# 10_RS232_1.net
KiCad netlist of a schematic drawn in Altium Designer
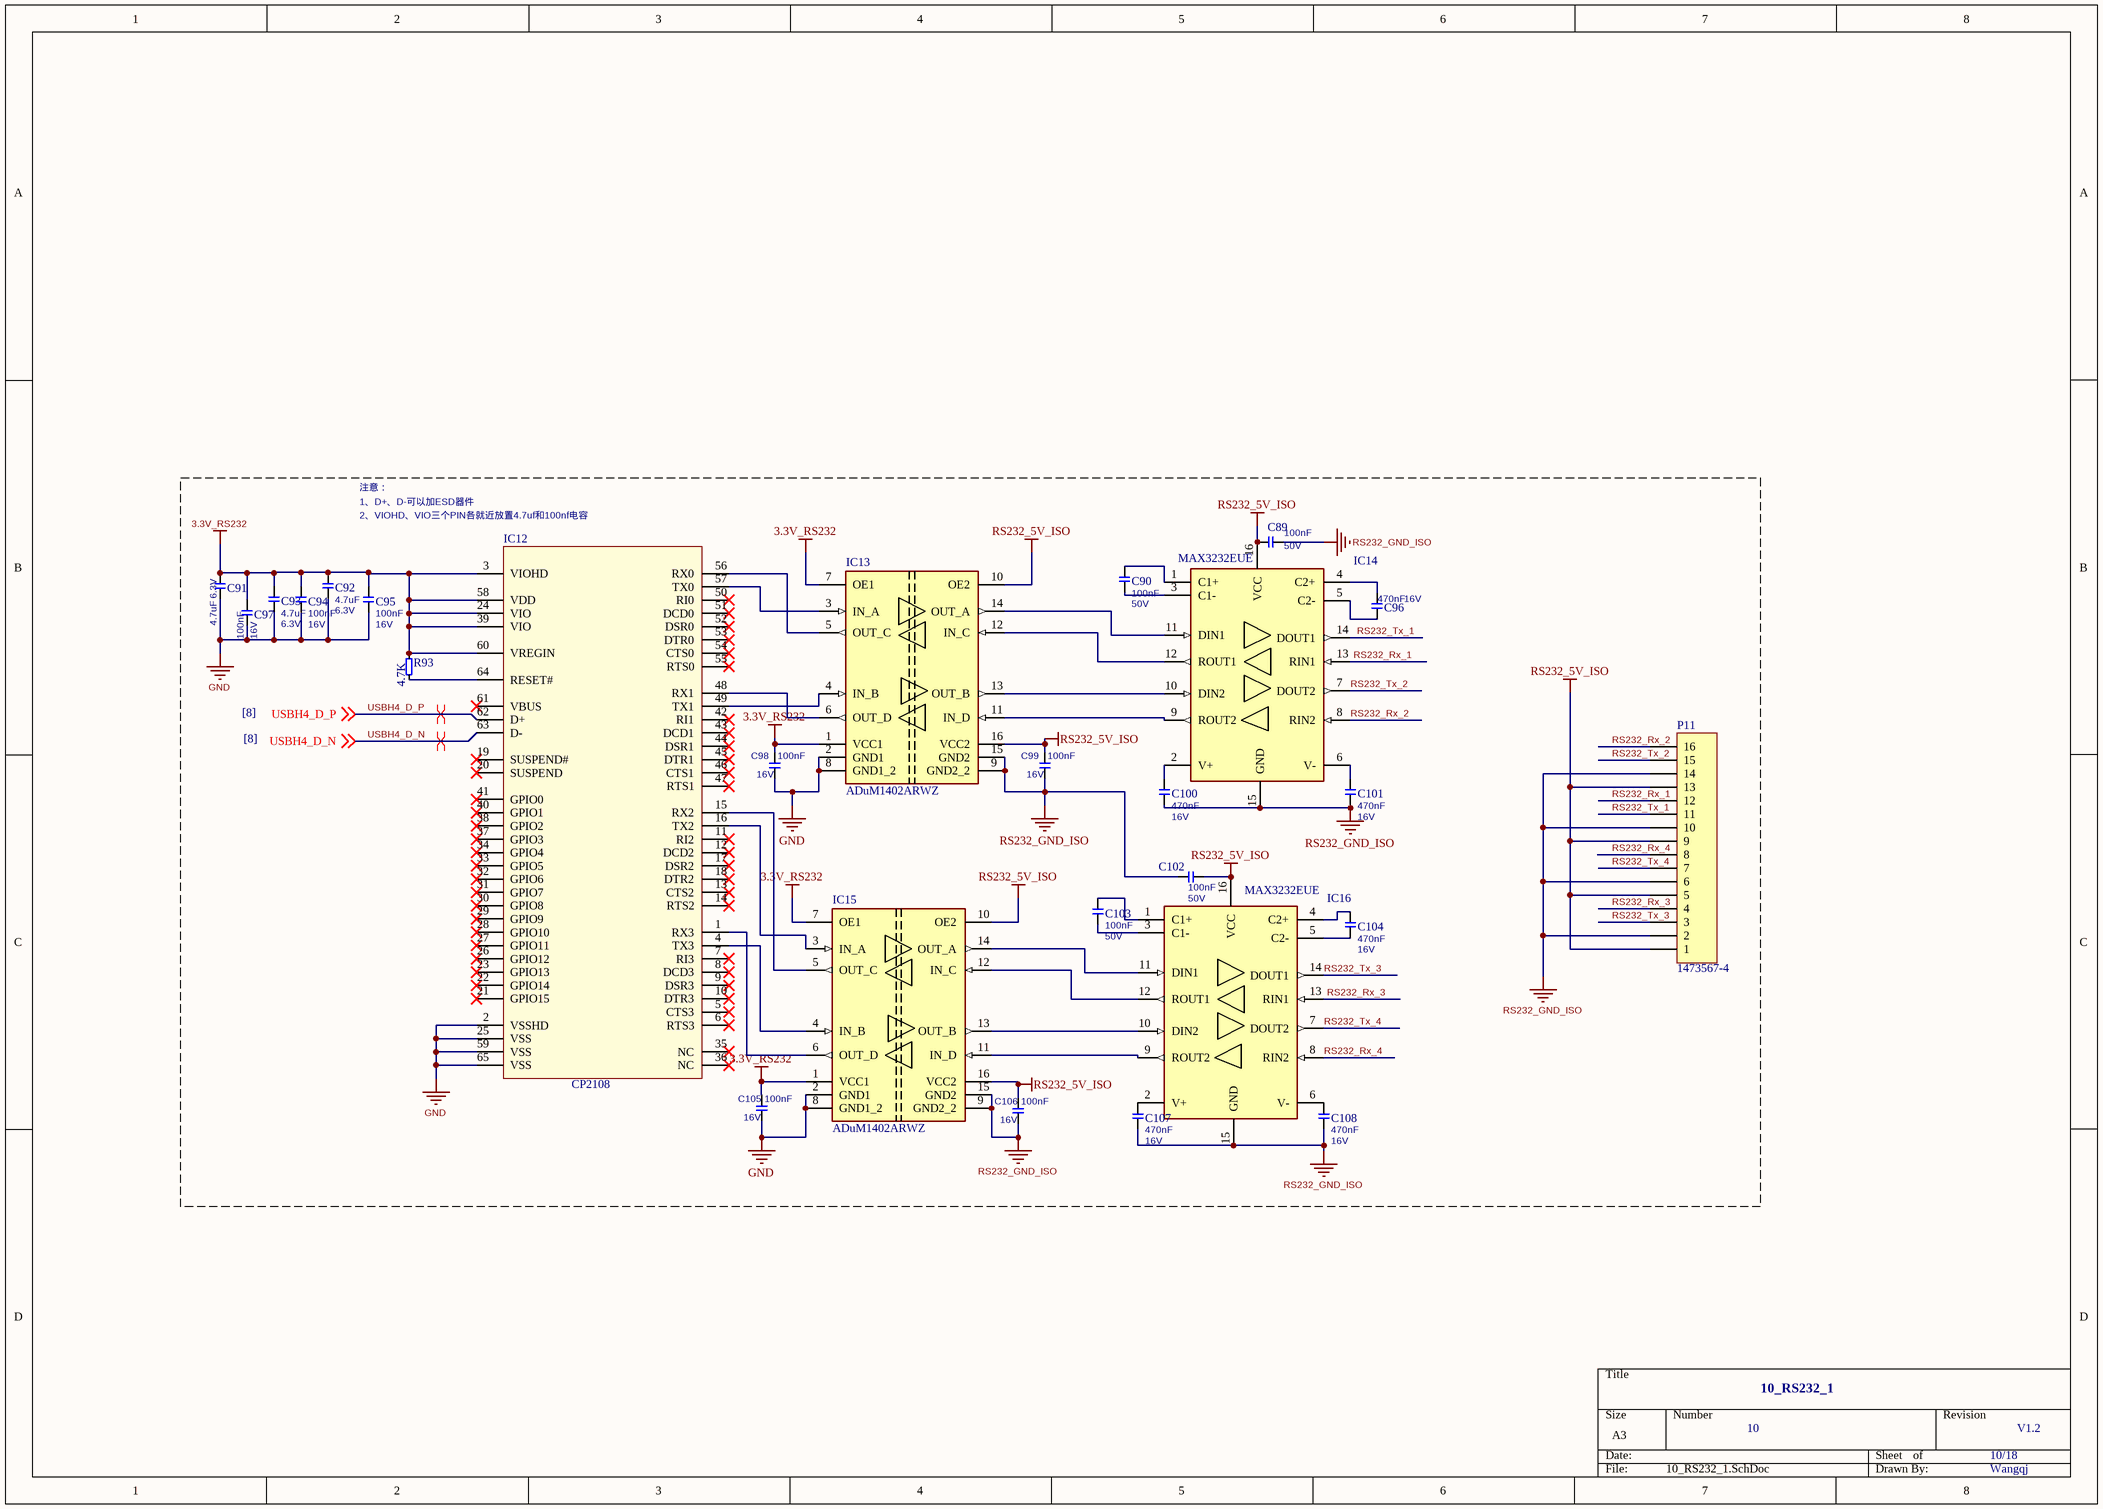
[diagram p0: 10_RS232_1.SchDoc]

(export (version "E")
  (design (tool "Eeschema 10.0.6"))
  (components
    (comp (ref "C89")
      (value "100nF")
      (footprint "T_CAPC0603X33N")
      (description "Capacitor Ceramic X7R 100nF 50V 20% 0603")
      (fields (field (name "TOLERANCE") "20%") (field (name "RATING") "50V"))
      (libsource (lib "Apalis Evaluation Board") (part "C-X7R-100nF-50V-20%-0603"))
    )
    (comp (ref "C90")
      (value "100nF")
      (footprint "T_CAPC0603X33N")
      (description "Capacitor Ceramic X7R 100nF 50V 20% 0603")
      (fields (field (name "TOLERANCE") "20%") (field (name "RATING") "50V"))
      (libsource (lib "Apalis Evaluation Board") (part "C-X7R-100nF-50V-20%-0603"))
    )
    (comp (ref "C91")
      (value "4.7uF")
      (footprint "T_CAPC0603X33N")
      (description "Capacitor Ceramic X5R 4.7uF 6.3V 20% 0603")
      (fields (field (name "TOLERANCE") "20%") (field (name "RATING") "6.3V"))
      (libsource (lib "Apalis Evaluation Board") (part "C-4.7uF-6.3V-20%-0603-X5R"))
    )
    (comp (ref "C92")
      (value "4.7uF")
      (footprint "T_CAPC0603X33N")
      (description "Capacitor Ceramic X5R 4.7uF 6.3V 20% 0603")
      (fields (field (name "TOLERANCE") "20%") (field (name "RATING") "6.3V"))
      (libsource (lib "Apalis Evaluation Board") (part "C-4.7uF-6.3V-20%-0603-X5R"))
    )
    (comp (ref "C93")
      (value "4.7uF")
      (footprint "T_CAPC0603X33N")
      (description "Capacitor Ceramic X5R 4.7uF 6.3V 20% 0603")
      (fields (field (name "TOLERANCE") "20%") (field (name "RATING") "6.3V"))
      (libsource (lib "Apalis Evaluation Board") (part "C-4.7uF-6.3V-20%-0603-X5R"))
    )
    (comp (ref "C94")
      (value "100nF")
      (footprint "T_CAPC0603X33N")
      (description "Capacitor Ceramic X7R 100nF 16V 10% 0603")
      (fields (field (name "TOLERANCE") "10%") (field (name "RATING") "16V"))
      (libsource (lib "Apalis Evaluation Board") (part "C-100nF-16V-10%-0603-X7R"))
    )
    (comp (ref "C95")
      (value "100nF")
      (footprint "T_CAPC0603X33N")
      (description "Capacitor Ceramic X7R 100nF 16V 10% 0603")
      (fields (field (name "TOLERANCE") "10%") (field (name "RATING") "16V"))
      (libsource (lib "Apalis Evaluation Board") (part "C-100nF-16V-10%-0603-X7R"))
    )
    (comp (ref "C96")
      (value "470nF")
      (footprint "T_CAPC0603X33N")
      (description "Capacitor Ceramic X7R 470nF 16V 10% 0603")
      (fields (field (name "TOLERANCE") "10%") (field (name "RATING") "16V"))
      (libsource (lib "Apalis Evaluation Board") (part "C-X7R-470nF-16V-10%-0603"))
    )
    (comp (ref "C97")
      (value "100nF")
      (footprint "T_CAPC0603X33N")
      (description "Capacitor Ceramic X7R 100nF 16V 10% 0603")
      (fields (field (name "TOLERANCE") "10%") (field (name "RATING") "16V"))
      (libsource (lib "Apalis Evaluation Board") (part "C-100nF-16V-10%-0603-X7R"))
    )
    (comp (ref "C98")
      (value "100nF")
      (footprint "T_CAPC0603X33N")
      (description "Capacitor Ceramic X7R 100nF 16V 10% 0603")
      (fields (field (name "TOLERANCE") "10%") (field (name "RATING") "16V"))
      (libsource (lib "Apalis Evaluation Board") (part "C-X7R-100nF-16V-10%-0603"))
    )
    (comp (ref "C99")
      (value "100nF")
      (footprint "T_CAPC0603X33N")
      (description "Capacitor Ceramic X7R 100nF 16V 10% 0603")
      (fields (field (name "TOLERANCE") "10%") (field (name "RATING") "16V"))
      (libsource (lib "Apalis Evaluation Board") (part "C-X7R-100nF-16V-10%-0603"))
    )
    (comp (ref "C100")
      (value "470nF")
      (footprint "T_CAPC0603X33N")
      (description "Capacitor Ceramic X7R 470nF 16V 10% 0603")
      (fields (field (name "TOLERANCE") "10%") (field (name "RATING") "16V"))
      (libsource (lib "Apalis Evaluation Board") (part "C-X7R-470nF-16V-10%-0603"))
    )
    (comp (ref "C101")
      (value "470nF")
      (footprint "T_CAPC0603X33N")
      (description "Capacitor Ceramic X7R 470nF 16V 10% 0603")
      (fields (field (name "TOLERANCE") "10%") (field (name "RATING") "16V"))
      (libsource (lib "Apalis Evaluation Board") (part "C-X7R-470nF-16V-10%-0603"))
    )
    (comp (ref "C102")
      (value "100nF")
      (footprint "T_CAPC0603X33N")
      (description "Capacitor Ceramic X7R 100nF 50V 20% 0603")
      (fields (field (name "TOLERANCE") "20%") (field (name "RATING") "50V"))
      (libsource (lib "Apalis Evaluation Board") (part "C-X7R-100nF-50V-20%-0603"))
    )
    (comp (ref "C103")
      (value "100nF")
      (footprint "T_CAPC0603X33N")
      (description "Capacitor Ceramic X7R 100nF 50V 20% 0603")
      (fields (field (name "TOLERANCE") "20%") (field (name "RATING") "50V"))
      (libsource (lib "Apalis Evaluation Board") (part "C-X7R-100nF-50V-20%-0603"))
    )
    (comp (ref "C104")
      (value "470nF")
      (footprint "T_CAPC0603X33N")
      (description "Capacitor Ceramic X7R 470nF 16V 10% 0603")
      (fields (field (name "TOLERANCE") "10%") (field (name "RATING") "16V"))
      (libsource (lib "Apalis Evaluation Board") (part "C-X7R-470nF-16V-10%-0603"))
    )
    (comp (ref "C105")
      (value "100nF")
      (footprint "T_CAPC0603X33N")
      (description "Capacitor Ceramic X7R 100nF 16V 10% 0603")
      (fields (field (name "TOLERANCE") "10%") (field (name "RATING") "16V"))
      (libsource (lib "Apalis Evaluation Board") (part "C-X7R-100nF-16V-10%-0603"))
    )
    (comp (ref "C106")
      (value "100nF")
      (footprint "T_CAPC0603X33N")
      (description "Capacitor Ceramic X7R 100nF 16V 10% 0603")
      (fields (field (name "TOLERANCE") "10%") (field (name "RATING") "16V"))
      (libsource (lib "Apalis Evaluation Board") (part "C-X7R-100nF-16V-10%-0603"))
    )
    (comp (ref "C107")
      (value "470nF")
      (footprint "T_CAPC0603X33N")
      (description "Capacitor Ceramic X7R 470nF 16V 10% 0603")
      (fields (field (name "TOLERANCE") "10%") (field (name "RATING") "16V"))
      (libsource (lib "Apalis Evaluation Board") (part "C-X7R-470nF-16V-10%-0603"))
    )
    (comp (ref "C108")
      (value "470nF")
      (footprint "T_CAPC0603X33N")
      (description "Capacitor Ceramic X7R 470nF 16V 10% 0603")
      (fields (field (name "TOLERANCE") "10%") (field (name "RATING") "16V"))
      (libsource (lib "Apalis Evaluation Board") (part "C-X7R-470nF-16V-10%-0603"))
    )
    (comp (ref "IC12")
      (value "CP2108")
      (footprint "QFN50P900X900X90_HS-65N")
      (description "Single-Chip USB To Quad UART Bridge")
      (fields (field (name "MANUCFACTURER PART NO.") "CP2108"))
      (libsource (lib "Apalis Evaluation Board") (part "IC-SILICON-CP2108"))
    )
    (comp (ref "IC13")
      (value "ADuM1402ARWZ")
      (footprint "T_AD_ADuM1300ARW")
      (description "Digital Isolator")
      (libsource (lib "Apalis Evaluation Board") (part "IC-AD-ADuM1402ARWZ"))
    )
    (comp (ref "IC14")
      (value "MAX3232EUE")
      (footprint "LC-TSSOP-16")
      (description "RS232")
      (libsource (lib "Apalis Evaluation Board") (part "IC-MAXIM-MAX3232"))
    )
    (comp (ref "IC15")
      (value "ADuM1402ARWZ")
      (footprint "T_AD_ADuM1300ARW")
      (description "Digital Isolator")
      (libsource (lib "Apalis Evaluation Board") (part "IC-AD-ADuM1402ARWZ"))
    )
    (comp (ref "IC16")
      (value "MAX3232EUE")
      (footprint "LC-TSSOP-16")
      (description "RS232")
      (libsource (lib "Apalis Evaluation Board") (part "IC-MAXIM-MAX3232"))
    )
    (comp (ref "P11")
      (value "1473567-4")
      (footprint "147-4")
      (description "泰科4P端子")
      (fields (field (name "PUBLISHER") "Altium Limited"))
      (libsource (lib "Miscellaneous Connectors") (part "MHDR1X16"))
    )
    (comp (ref "R93")
      (value "4.7K")
      (footprint "t_RESC0603X30N")
      (description "Resistor 4.7 Kohm 63mW 5% 0603")
      (fields (field (name "TOLERANCE") "5%"))
      (libsource (lib "Apalis Evaluation Board") (part "R-4.7kR-63mW-5%-0603"))
    )
  )
  (nets
    (net (code "1") (name "/RS232_Rx_1") (class "Default")
      (node (ref "IC14") (pin "13") (pinfunction "RIN1_13") (pintype "input"))
      (node (ref "P11") (pin "12") (pinfunction "12_12") (pintype "passive"))
    )
    (net (code "2") (name "/RS232_Rx_2") (class "Default")
      (node (ref "IC14") (pin "8") (pinfunction "RIN2_8") (pintype "input"))
      (node (ref "P11") (pin "16") (pinfunction "16_16") (pintype "passive"))
    )
    (net (code "3") (name "/RS232_Rx_3") (class "Default")
      (node (ref "IC16") (pin "13") (pinfunction "RIN1_13") (pintype "input"))
      (node (ref "P11") (pin "4") (pinfunction "4_4") (pintype "passive"))
    )
    (net (code "4") (name "/RS232_Rx_4") (class "Default")
      (node (ref "IC16") (pin "8") (pinfunction "RIN2_8") (pintype "input"))
      (node (ref "P11") (pin "8") (pinfunction "8_8") (pintype "passive"))
    )
    (net (code "5") (name "/RS232_Tx_1") (class "Default")
      (node (ref "IC14") (pin "14") (pinfunction "DOUT1_14") (pintype "output"))
      (node (ref "P11") (pin "11") (pinfunction "11_11") (pintype "passive"))
    )
    (net (code "6") (name "/RS232_Tx_2") (class "Default")
      (node (ref "IC14") (pin "7") (pinfunction "DOUT2_7") (pintype "output"))
      (node (ref "P11") (pin "15") (pinfunction "15_15") (pintype "passive"))
    )
    (net (code "7") (name "/RS232_Tx_3") (class "Default")
      (node (ref "IC16") (pin "14") (pinfunction "DOUT1_14") (pintype "output"))
      (node (ref "P11") (pin "3") (pinfunction "3_3") (pintype "passive"))
    )
    (net (code "8") (name "/RS232_Tx_4") (class "Default")
      (node (ref "IC16") (pin "7") (pinfunction "DOUT2_7") (pintype "output"))
      (node (ref "P11") (pin "7") (pinfunction "7_7") (pintype "passive"))
    )
    (net (code "9") (name "3.3V_RS232") (class "Default")
      (node (ref "C105") (pin "2") (pinfunction "2_2") (pintype "passive"))
      (node (ref "C91") (pin "2") (pinfunction "2_2") (pintype "passive"))
      (node (ref "C92") (pin "2") (pinfunction "2_2") (pintype "passive"))
      (node (ref "C93") (pin "2") (pinfunction "2_2") (pintype "passive"))
      (node (ref "C94") (pin "2") (pinfunction "2_2") (pintype "passive"))
      (node (ref "C95") (pin "2") (pinfunction "2_2") (pintype "passive"))
      (node (ref "C97") (pin "2") (pinfunction "2_2") (pintype "passive"))
      (node (ref "C98") (pin "2") (pinfunction "2_2") (pintype "passive"))
      (node (ref "IC12") (pin "24") (pinfunction "VIO_24") (pintype "power_in"))
      (node (ref "IC12") (pin "3") (pinfunction "VIOHD_3") (pintype "power_in"))
      (node (ref "IC12") (pin "39") (pinfunction "VIO_39") (pintype "passive"))
      (node (ref "IC12") (pin "58") (pinfunction "VDD_58") (pintype "passive"))
      (node (ref "IC12") (pin "60") (pinfunction "VREGIN_60") (pintype "passive"))
      (node (ref "IC13") (pin "1") (pinfunction "VCC1_1") (pintype "passive"))
      (node (ref "IC13") (pin "7") (pinfunction "OE1_7") (pintype "passive"))
      (node (ref "IC15") (pin "1") (pinfunction "VCC1_1") (pintype "passive"))
      (node (ref "IC15") (pin "7") (pinfunction "OE1_7") (pintype "passive"))
      (node (ref "R93") (pin "2") (pinfunction "2_2") (pintype "passive"))
    )
    (net (code "10") (name "GND") (class "Default")
      (node (ref "C105") (pin "1") (pinfunction "1_1") (pintype "passive"))
      (node (ref "C91") (pin "1") (pinfunction "1_1") (pintype "passive"))
      (node (ref "C92") (pin "1") (pinfunction "1_1") (pintype "passive"))
      (node (ref "C93") (pin "1") (pinfunction "1_1") (pintype "passive"))
      (node (ref "C94") (pin "1") (pinfunction "1_1") (pintype "passive"))
      (node (ref "C95") (pin "1") (pinfunction "1_1") (pintype "passive"))
      (node (ref "C97") (pin "1") (pinfunction "1_1") (pintype "passive"))
      (node (ref "C98") (pin "1") (pinfunction "1_1") (pintype "passive"))
      (node (ref "IC12") (pin "2") (pinfunction "VSSHD_2") (pintype "passive"))
      (node (ref "IC12") (pin "25") (pinfunction "VSS_25") (pintype "power_in"))
      (node (ref "IC12") (pin "59") (pinfunction "VSS_59") (pintype "passive"))
      (node (ref "IC12") (pin "65") (pinfunction "VSS_65") (pintype "passive"))
      (node (ref "IC13") (pin "2") (pinfunction "GND1_2") (pintype "power_in"))
      (node (ref "IC13") (pin "8") (pinfunction "GND1_2_8") (pintype "power_in"))
      (node (ref "IC15") (pin "2") (pinfunction "GND1_2") (pintype "power_in"))
      (node (ref "IC15") (pin "8") (pinfunction "GND1_2_8") (pintype "power_in"))
    )
    (net (code "11") (name "Net-(IC12-RESET#)") (class "Default")
      (node (ref "IC12") (pin "64") (pinfunction "RESET#_64") (pintype "passive"))
      (node (ref "R93") (pin "1") (pinfunction "1_1") (pintype "passive"))
    )
    (net (code "12") (name "Net-(IC12-RX0)") (class "Default")
      (node (ref "IC12") (pin "56") (pinfunction "RX0_56") (pintype "passive"))
      (node (ref "IC13") (pin "5") (pinfunction "OUT_C_5") (pintype "output"))
    )
    (net (code "13") (name "Net-(IC12-RX1)") (class "Default")
      (node (ref "IC12") (pin "48") (pinfunction "RX1_48") (pintype "passive"))
      (node (ref "IC13") (pin "6") (pinfunction "OUT_D_6") (pintype "output"))
    )
    (net (code "14") (name "Net-(IC12-RX2)") (class "Default")
      (node (ref "IC12") (pin "15") (pinfunction "RX2_15") (pintype "passive"))
      (node (ref "IC15") (pin "5") (pinfunction "OUT_C_5") (pintype "output"))
    )
    (net (code "15") (name "Net-(IC12-RX3)") (class "Default")
      (node (ref "IC12") (pin "1") (pinfunction "RX3_1") (pintype "passive"))
      (node (ref "IC15") (pin "6") (pinfunction "OUT_D_6") (pintype "output"))
    )
    (net (code "16") (name "Net-(IC12-TX0)") (class "Default")
      (node (ref "IC12") (pin "57") (pinfunction "TX0_57") (pintype "passive"))
      (node (ref "IC13") (pin "3") (pinfunction "IN_A_3") (pintype "input"))
    )
    (net (code "17") (name "Net-(IC12-TX1)") (class "Default")
      (node (ref "IC12") (pin "49") (pinfunction "TX1_49") (pintype "passive"))
      (node (ref "IC13") (pin "4") (pinfunction "IN_B_4") (pintype "input"))
    )
    (net (code "18") (name "Net-(IC12-TX2)") (class "Default")
      (node (ref "IC12") (pin "16") (pinfunction "TX2_16") (pintype "passive"))
      (node (ref "IC15") (pin "3") (pinfunction "IN_A_3") (pintype "input"))
    )
    (net (code "19") (name "Net-(IC12-TX3)") (class "Default")
      (node (ref "IC12") (pin "4") (pinfunction "TX3_4") (pintype "passive"))
      (node (ref "IC15") (pin "4") (pinfunction "IN_B_4") (pintype "input"))
    )
    (net (code "20") (name "Net-(IC13-IN_C)") (class "Default")
      (node (ref "IC13") (pin "12") (pinfunction "IN_C_12") (pintype "input"))
      (node (ref "IC14") (pin "12") (pinfunction "ROUT1_12") (pintype "output"))
    )
    (net (code "21") (name "Net-(IC13-IN_D)") (class "Default")
      (node (ref "IC13") (pin "11") (pinfunction "IN_D_11") (pintype "input"))
      (node (ref "IC14") (pin "9") (pinfunction "ROUT2_9") (pintype "output"))
    )
    (net (code "22") (name "Net-(IC13-OUT_A)") (class "Default")
      (node (ref "IC13") (pin "14") (pinfunction "OUT_A_14") (pintype "output"))
      (node (ref "IC14") (pin "11") (pinfunction "DIN1_11") (pintype "input"))
    )
    (net (code "23") (name "Net-(IC13-OUT_B)") (class "Default")
      (node (ref "IC13") (pin "13") (pinfunction "OUT_B_13") (pintype "output"))
      (node (ref "IC14") (pin "10") (pinfunction "DIN2_10") (pintype "input"))
    )
    (net (code "24") (name "Net-(IC14-C1+)") (class "Default")
      (node (ref "C90") (pin "2") (pinfunction "2_2") (pintype "passive"))
      (node (ref "IC14") (pin "1") (pinfunction "C1+_1") (pintype "passive"))
    )
    (net (code "25") (name "Net-(IC14-C1-)") (class "Default")
      (node (ref "C90") (pin "1") (pinfunction "1_1") (pintype "passive"))
      (node (ref "IC14") (pin "3") (pinfunction "C1-_3") (pintype "power_in"))
    )
    (net (code "26") (name "Net-(IC14-C2+)") (class "Default")
      (node (ref "C96") (pin "2") (pinfunction "2_2") (pintype "passive"))
      (node (ref "IC14") (pin "4") (pinfunction "C2+_4") (pintype "passive"))
    )
    (net (code "27") (name "Net-(IC14-C2-)") (class "Default")
      (node (ref "C96") (pin "1") (pinfunction "1_1") (pintype "passive"))
      (node (ref "IC14") (pin "5") (pinfunction "C2-_5") (pintype "power_in"))
    )
    (net (code "28") (name "Net-(IC14-V+)") (class "Default")
      (node (ref "C100") (pin "2") (pinfunction "2_2") (pintype "passive"))
      (node (ref "IC14") (pin "2") (pinfunction "V+_2") (pintype "passive"))
    )
    (net (code "29") (name "Net-(IC14-V-)") (class "Default")
      (node (ref "C101") (pin "2") (pinfunction "2_2") (pintype "passive"))
      (node (ref "IC14") (pin "6") (pinfunction "V-_6") (pintype "passive"))
    )
    (net (code "30") (name "Net-(IC15-IN_C)") (class "Default")
      (node (ref "IC15") (pin "12") (pinfunction "IN_C_12") (pintype "input"))
      (node (ref "IC16") (pin "12") (pinfunction "ROUT1_12") (pintype "output"))
    )
    (net (code "31") (name "Net-(IC15-IN_D)") (class "Default")
      (node (ref "IC15") (pin "11") (pinfunction "IN_D_11") (pintype "input"))
      (node (ref "IC16") (pin "9") (pinfunction "ROUT2_9") (pintype "output"))
    )
    (net (code "32") (name "Net-(IC15-OUT_A)") (class "Default")
      (node (ref "IC15") (pin "14") (pinfunction "OUT_A_14") (pintype "output"))
      (node (ref "IC16") (pin "11") (pinfunction "DIN1_11") (pintype "input"))
    )
    (net (code "33") (name "Net-(IC15-OUT_B)") (class "Default")
      (node (ref "IC15") (pin "13") (pinfunction "OUT_B_13") (pintype "output"))
      (node (ref "IC16") (pin "10") (pinfunction "DIN2_10") (pintype "input"))
    )
    (net (code "34") (name "Net-(IC16-C1+)") (class "Default")
      (node (ref "C103") (pin "2") (pinfunction "2_2") (pintype "passive"))
      (node (ref "IC16") (pin "1") (pinfunction "C1+_1") (pintype "passive"))
    )
    (net (code "35") (name "Net-(IC16-C1-)") (class "Default")
      (node (ref "C103") (pin "1") (pinfunction "1_1") (pintype "passive"))
      (node (ref "IC16") (pin "3") (pinfunction "C1-_3") (pintype "power_in"))
    )
    (net (code "36") (name "Net-(IC16-C2+)") (class "Default")
      (node (ref "C104") (pin "2") (pinfunction "2_2") (pintype "passive"))
      (node (ref "IC16") (pin "4") (pinfunction "C2+_4") (pintype "passive"))
    )
    (net (code "37") (name "Net-(IC16-C2-)") (class "Default")
      (node (ref "C104") (pin "1") (pinfunction "1_1") (pintype "passive"))
      (node (ref "IC16") (pin "5") (pinfunction "C2-_5") (pintype "power_in"))
    )
    (net (code "38") (name "Net-(IC16-V+)") (class "Default")
      (node (ref "C107") (pin "2") (pinfunction "2_2") (pintype "passive"))
      (node (ref "IC16") (pin "2") (pinfunction "V+_2") (pintype "passive"))
    )
    (net (code "39") (name "Net-(IC16-V-)") (class "Default")
      (node (ref "C108") (pin "2") (pinfunction "2_2") (pintype "passive"))
      (node (ref "IC16") (pin "6") (pinfunction "V-_6") (pintype "passive"))
    )
    (net (code "40") (name "RS232_5V_ISO") (class "Default")
      (node (ref "C102") (pin "1") (pinfunction "1_1") (pintype "passive"))
      (node (ref "C106") (pin "2") (pinfunction "2_2") (pintype "passive"))
      (node (ref "C89") (pin "2") (pinfunction "2_2") (pintype "passive"))
      (node (ref "C99") (pin "2") (pinfunction "2_2") (pintype "passive"))
      (node (ref "IC13") (pin "10") (pinfunction "OE2_10") (pintype "passive"))
      (node (ref "IC13") (pin "16") (pinfunction "VCC2_16") (pintype "passive"))
      (node (ref "IC14") (pin "16") (pinfunction "VCC_16") (pintype "power_in"))
      (node (ref "IC15") (pin "10") (pinfunction "OE2_10") (pintype "passive"))
      (node (ref "IC15") (pin "16") (pinfunction "VCC2_16") (pintype "passive"))
      (node (ref "IC16") (pin "16") (pinfunction "VCC_16") (pintype "power_in"))
      (node (ref "P11") (pin "1") (pinfunction "1_1") (pintype "passive"))
      (node (ref "P11") (pin "13") (pinfunction "13_13") (pintype "passive"))
      (node (ref "P11") (pin "5") (pinfunction "5_5") (pintype "passive"))
      (node (ref "P11") (pin "9") (pinfunction "9_9") (pintype "passive"))
    )
    (net (code "41") (name "RS232_GND_ISO") (class "Default")
      (node (ref "C100") (pin "1") (pinfunction "1_1") (pintype "passive"))
      (node (ref "C101") (pin "1") (pinfunction "1_1") (pintype "passive"))
      (node (ref "C102") (pin "2") (pinfunction "2_2") (pintype "passive"))
      (node (ref "C106") (pin "1") (pinfunction "1_1") (pintype "passive"))
      (node (ref "C107") (pin "1") (pinfunction "1_1") (pintype "passive"))
      (node (ref "C108") (pin "1") (pinfunction "1_1") (pintype "passive"))
      (node (ref "C89") (pin "1") (pinfunction "1_1") (pintype "passive"))
      (node (ref "C99") (pin "1") (pinfunction "1_1") (pintype "passive"))
      (node (ref "IC13") (pin "15") (pinfunction "GND2_15") (pintype "power_in"))
      (node (ref "IC13") (pin "9") (pinfunction "GND2_2_9") (pintype "power_in"))
      (node (ref "IC14") (pin "15") (pinfunction "GND_15") (pintype "power_in"))
      (node (ref "IC15") (pin "15") (pinfunction "GND2_15") (pintype "power_in"))
      (node (ref "IC15") (pin "9") (pinfunction "GND2_2_9") (pintype "power_in"))
      (node (ref "IC16") (pin "15") (pinfunction "GND_15") (pintype "power_in"))
      (node (ref "P11") (pin "10") (pinfunction "10_10") (pintype "passive"))
      (node (ref "P11") (pin "14") (pinfunction "14_14") (pintype "passive"))
      (node (ref "P11") (pin "2") (pinfunction "2_2") (pintype "passive"))
      (node (ref "P11") (pin "6") (pinfunction "6_6") (pintype "passive"))
    )
    (net (code "42") (name "USBH4_D_N") (class "Default")
      (node (ref "IC12") (pin "63") (pinfunction "D-_63") (pintype "passive"))
    )
    (net (code "43") (name "USBH4_D_P") (class "Default")
      (node (ref "IC12") (pin "62") (pinfunction "D+_62") (pintype "passive"))
    )
    (net (code "44") (name "unconnected-(IC12-CTS0-Pad54)") (class "Default")
      (node (ref "IC12") (pin "54") (pinfunction "CTS0_54") (pintype "passive+no_connect"))
    )
    (net (code "45") (name "unconnected-(IC12-CTS1-Pad46)") (class "Default")
      (node (ref "IC12") (pin "46") (pinfunction "CTS1_46") (pintype "passive+no_connect"))
    )
    (net (code "46") (name "unconnected-(IC12-CTS2-Pad13)") (class "Default")
      (node (ref "IC12") (pin "13") (pinfunction "CTS2_13") (pintype "passive+no_connect"))
    )
    (net (code "47") (name "unconnected-(IC12-CTS3-Pad5)") (class "Default")
      (node (ref "IC12") (pin "5") (pinfunction "CTS3_5") (pintype "passive+no_connect"))
    )
    (net (code "48") (name "unconnected-(IC12-DCD0-Pad51)") (class "Default")
      (node (ref "IC12") (pin "51") (pinfunction "DCD0_51") (pintype "passive+no_connect"))
    )
    (net (code "49") (name "unconnected-(IC12-DCD1-Pad43)") (class "Default")
      (node (ref "IC12") (pin "43") (pinfunction "DCD1_43") (pintype "passive+no_connect"))
    )
    (net (code "50") (name "unconnected-(IC12-DCD2-Pad12)") (class "Default")
      (node (ref "IC12") (pin "12") (pinfunction "DCD2_12") (pintype "passive+no_connect"))
    )
    (net (code "51") (name "unconnected-(IC12-DCD3-Pad8)") (class "Default")
      (node (ref "IC12") (pin "8") (pinfunction "DCD3_8") (pintype "passive+no_connect"))
    )
    (net (code "52") (name "unconnected-(IC12-DSR0-Pad52)") (class "Default")
      (node (ref "IC12") (pin "52") (pinfunction "DSR0_52") (pintype "passive+no_connect"))
    )
    (net (code "53") (name "unconnected-(IC12-DSR1-Pad44)") (class "Default")
      (node (ref "IC12") (pin "44") (pinfunction "DSR1_44") (pintype "passive+no_connect"))
    )
    (net (code "54") (name "unconnected-(IC12-DSR2-Pad17)") (class "Default")
      (node (ref "IC12") (pin "17") (pinfunction "DSR2_17") (pintype "passive+no_connect"))
    )
    (net (code "55") (name "unconnected-(IC12-DSR3-Pad9)") (class "Default")
      (node (ref "IC12") (pin "9") (pinfunction "DSR3_9") (pintype "passive+no_connect"))
    )
    (net (code "56") (name "unconnected-(IC12-DTR0-Pad53)") (class "Default")
      (node (ref "IC12") (pin "53") (pinfunction "DTR0_53") (pintype "passive+no_connect"))
    )
    (net (code "57") (name "unconnected-(IC12-DTR1-Pad45)") (class "Default")
      (node (ref "IC12") (pin "45") (pinfunction "DTR1_45") (pintype "passive+no_connect"))
    )
    (net (code "58") (name "unconnected-(IC12-DTR2-Pad18)") (class "Default")
      (node (ref "IC12") (pin "18") (pinfunction "DTR2_18") (pintype "passive+no_connect"))
    )
    (net (code "59") (name "unconnected-(IC12-DTR3-Pad10)") (class "Default")
      (node (ref "IC12") (pin "10") (pinfunction "DTR3_10") (pintype "passive+no_connect"))
    )
    (net (code "60") (name "unconnected-(IC12-GPIO0-Pad41)") (class "Default")
      (node (ref "IC12") (pin "41") (pinfunction "GPIO0_41") (pintype "passive+no_connect"))
    )
    (net (code "61") (name "unconnected-(IC12-GPIO1-Pad40)") (class "Default")
      (node (ref "IC12") (pin "40") (pinfunction "GPIO1_40") (pintype "passive+no_connect"))
    )
    (net (code "62") (name "unconnected-(IC12-GPIO2-Pad38)") (class "Default")
      (node (ref "IC12") (pin "38") (pinfunction "GPIO2_38") (pintype "passive+no_connect"))
    )
    (net (code "63") (name "unconnected-(IC12-GPIO3-Pad37)") (class "Default")
      (node (ref "IC12") (pin "37") (pinfunction "GPIO3_37") (pintype "passive+no_connect"))
    )
    (net (code "64") (name "unconnected-(IC12-GPIO4-Pad34)") (class "Default")
      (node (ref "IC12") (pin "34") (pinfunction "GPIO4_34") (pintype "passive+no_connect"))
    )
    (net (code "65") (name "unconnected-(IC12-GPIO5-Pad33)") (class "Default")
      (node (ref "IC12") (pin "33") (pinfunction "GPIO5_33") (pintype "passive+no_connect"))
    )
    (net (code "66") (name "unconnected-(IC12-GPIO6-Pad32)") (class "Default")
      (node (ref "IC12") (pin "32") (pinfunction "GPIO6_32") (pintype "passive+no_connect"))
    )
    (net (code "67") (name "unconnected-(IC12-GPIO7-Pad31)") (class "Default")
      (node (ref "IC12") (pin "31") (pinfunction "GPIO7_31") (pintype "passive+no_connect"))
    )
    (net (code "68") (name "unconnected-(IC12-GPIO8-Pad30)") (class "Default")
      (node (ref "IC12") (pin "30") (pinfunction "GPIO8_30") (pintype "passive+no_connect"))
    )
    (net (code "69") (name "unconnected-(IC12-GPIO9-Pad29)") (class "Default")
      (node (ref "IC12") (pin "29") (pinfunction "GPIO9_29") (pintype "passive+no_connect"))
    )
    (net (code "70") (name "unconnected-(IC12-GPIO10-Pad28)") (class "Default")
      (node (ref "IC12") (pin "28") (pinfunction "GPIO10_28") (pintype "passive+no_connect"))
    )
    (net (code "71") (name "unconnected-(IC12-GPIO11-Pad27)") (class "Default")
      (node (ref "IC12") (pin "27") (pinfunction "GPIO11_27") (pintype "passive+no_connect"))
    )
    (net (code "72") (name "unconnected-(IC12-GPIO12-Pad26)") (class "Default")
      (node (ref "IC12") (pin "26") (pinfunction "GPIO12_26") (pintype "passive+no_connect"))
    )
    (net (code "73") (name "unconnected-(IC12-GPIO13-Pad23)") (class "Default")
      (node (ref "IC12") (pin "23") (pinfunction "GPIO13_23") (pintype "passive+no_connect"))
    )
    (net (code "74") (name "unconnected-(IC12-GPIO14-Pad22)") (class "Default")
      (node (ref "IC12") (pin "22") (pinfunction "GPIO14_22") (pintype "passive+no_connect"))
    )
    (net (code "75") (name "unconnected-(IC12-GPIO15-Pad21)") (class "Default")
      (node (ref "IC12") (pin "21") (pinfunction "GPIO15_21") (pintype "passive+no_connect"))
    )
    (net (code "76") (name "unconnected-(IC12-NC-Pad35)") (class "Default")
      (node (ref "IC12") (pin "35") (pinfunction "NC_35") (pintype "passive+no_connect"))
    )
    (net (code "77") (name "unconnected-(IC12-NC-Pad36)") (class "Default")
      (node (ref "IC12") (pin "36") (pinfunction "NC_36") (pintype "passive+no_connect"))
    )
    (net (code "78") (name "unconnected-(IC12-RI0-Pad50)") (class "Default")
      (node (ref "IC12") (pin "50") (pinfunction "RI0_50") (pintype "passive+no_connect"))
    )
    (net (code "79") (name "unconnected-(IC12-RI1-Pad42)") (class "Default")
      (node (ref "IC12") (pin "42") (pinfunction "RI1_42") (pintype "passive+no_connect"))
    )
    (net (code "80") (name "unconnected-(IC12-RI2-Pad11)") (class "Default")
      (node (ref "IC12") (pin "11") (pinfunction "RI2_11") (pintype "passive+no_connect"))
    )
    (net (code "81") (name "unconnected-(IC12-RI3-Pad7)") (class "Default")
      (node (ref "IC12") (pin "7") (pinfunction "RI3_7") (pintype "passive+no_connect"))
    )
    (net (code "82") (name "unconnected-(IC12-RTS0-Pad55)") (class "Default")
      (node (ref "IC12") (pin "55") (pinfunction "RTS0_55") (pintype "passive+no_connect"))
    )
    (net (code "83") (name "unconnected-(IC12-RTS1-Pad47)") (class "Default")
      (node (ref "IC12") (pin "47") (pinfunction "RTS1_47") (pintype "passive+no_connect"))
    )
    (net (code "84") (name "unconnected-(IC12-RTS2-Pad14)") (class "Default")
      (node (ref "IC12") (pin "14") (pinfunction "RTS2_14") (pintype "passive+no_connect"))
    )
    (net (code "85") (name "unconnected-(IC12-RTS3-Pad6)") (class "Default")
      (node (ref "IC12") (pin "6") (pinfunction "RTS3_6") (pintype "passive+no_connect"))
    )
    (net (code "86") (name "unconnected-(IC12-SUSPEND#-Pad19)") (class "Default")
      (node (ref "IC12") (pin "19") (pinfunction "SUSPEND#_19") (pintype "passive+no_connect"))
    )
    (net (code "87") (name "unconnected-(IC12-SUSPEND-Pad20)") (class "Default")
      (node (ref "IC12") (pin "20") (pinfunction "SUSPEND_20") (pintype "passive+no_connect"))
    )
    (net (code "88") (name "unconnected-(IC12-VBUS-Pad61)") (class "Default")
      (node (ref "IC12") (pin "61") (pinfunction "VBUS_61") (pintype "passive+no_connect"))
    )
  )
)
